# IMX_Power_Regulation.net
KiCad netlist of a schematic drawn in Altium Designer
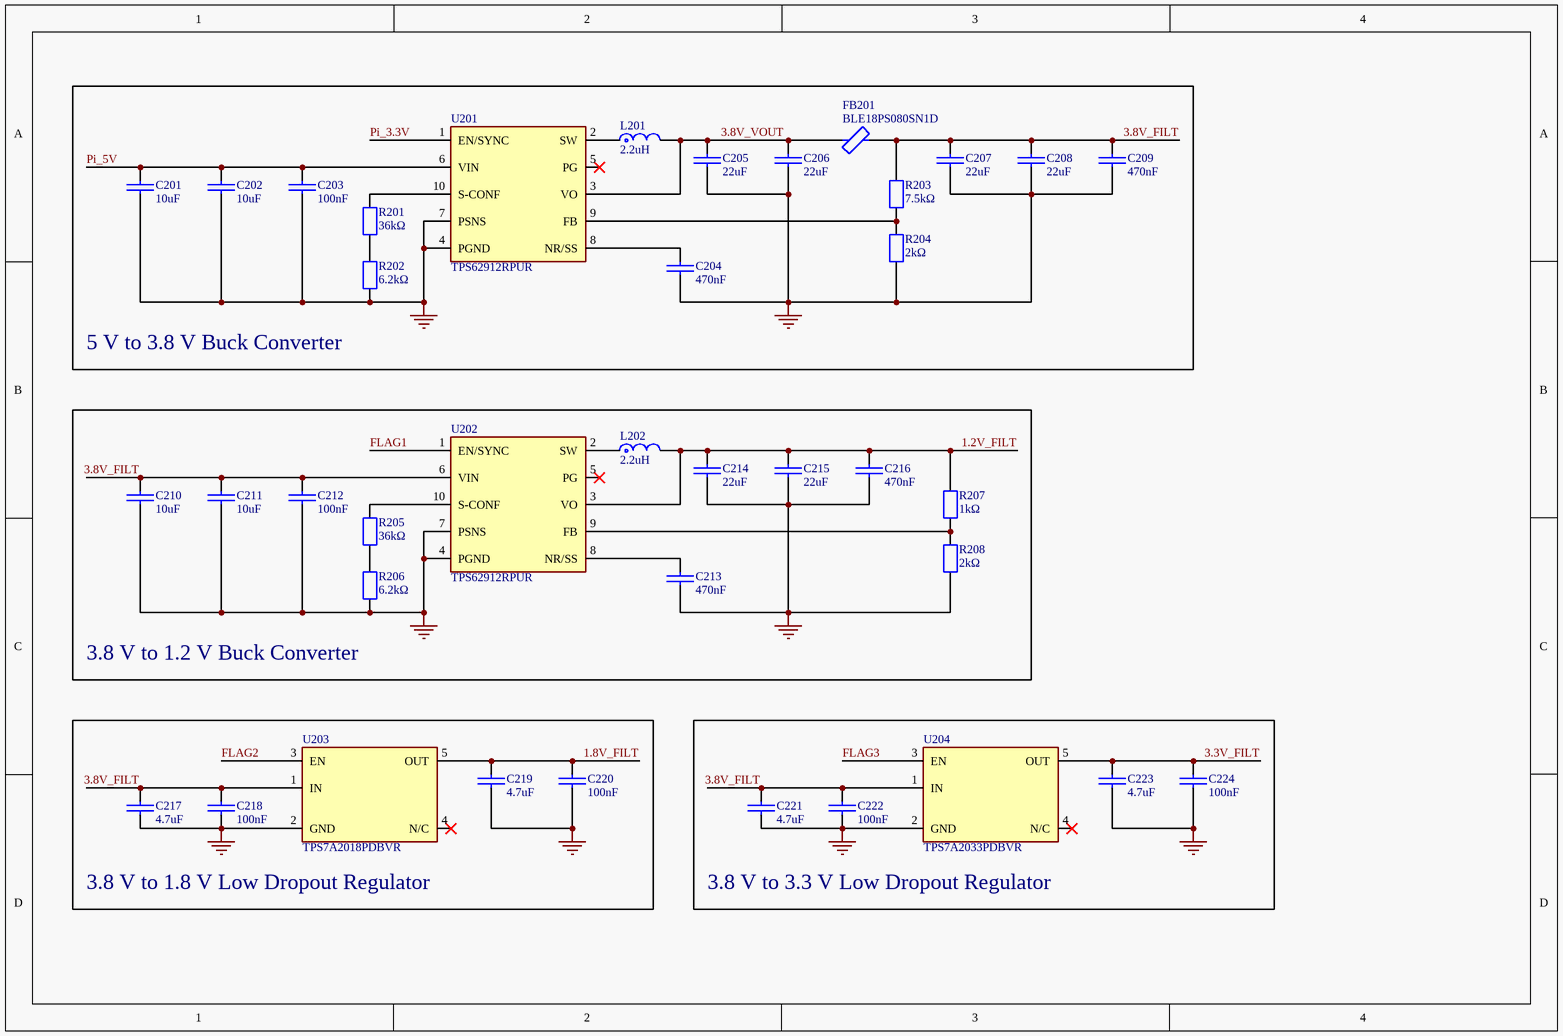
[diagram p0: IMX_Power Regulation.SchDoc]

(export (version "E")
  (design (tool "Eeschema 10.0.6"))
  (components
    (comp (ref "C201")
      (value "10uF")
      (footprint "Capacitor, 0603")
      (description "Ceramic Capacitor, 10V, 10% +/- Tol, X7R, 10uF, SMD, 0603, #GRM188Z71A106KA73D, JLC#C2959727")
      (libsource (lib "Component Library") (part "Capacitor, 0603, 10uF"))
    )
    (comp (ref "C202")
      (value "10uF")
      (footprint "Capacitor, 0603")
      (description "Ceramic Capacitor, 10V, 10% +/- Tol, X7R, 10uF, SMD, 0603, #GRM188Z71A106KA73D, JLC#C2959727")
      (libsource (lib "Component Library") (part "Capacitor, 0603, 10uF"))
    )
    (comp (ref "C203")
      (value "100nF")
      (footprint "Capacitor, 0402")
      (description "Ceramic Capacitor, 16V, 10% +/- Tol, X7R, 0.1uF, SMD, 0402, #CL05B104KO5NNNC, JLC#C1525")
      (libsource (lib "Component Library") (part "Capacitor, 0402, 100nF"))
    )
    (comp (ref "C204")
      (value "470nF")
      (footprint "Capacitor, 0402")
      (libsource (lib "Component Library") (part "Capacitor, 0402, 470nF"))
    )
    (comp (ref "C205")
      (value "22uF")
      (footprint "Capacitor, 0805")
      (libsource (lib "Component Library") (part "Capacitor, 0805, 22uF, X5R"))
    )
    (comp (ref "C206")
      (value "22uF")
      (footprint "Capacitor, 0805")
      (libsource (lib "Component Library") (part "Capacitor, 0805, 22uF, X5R"))
    )
    (comp (ref "C207")
      (value "22uF")
      (footprint "Capacitor, 0805")
      (libsource (lib "Component Library") (part "Capacitor, 0805, 22uF, X5R"))
    )
    (comp (ref "C208")
      (value "22uF")
      (footprint "Capacitor, 0805")
      (libsource (lib "Component Library") (part "Capacitor, 0805, 22uF, X5R"))
    )
    (comp (ref "C209")
      (value "470nF")
      (footprint "Capacitor, 0402")
      (libsource (lib "Component Library") (part "Capacitor, 0402, 470nF"))
    )
    (comp (ref "C210")
      (value "10uF")
      (footprint "Capacitor, 0603")
      (description "Ceramic Capacitor, 10V, 10% +/- Tol, X7R, 10uF, SMD, 0603, #GRM188Z71A106KA73D, JLC#C2959727")
      (libsource (lib "Component Library") (part "Capacitor, 0603, 10uF"))
    )
    (comp (ref "C211")
      (value "10uF")
      (footprint "Capacitor, 0603")
      (description "Ceramic Capacitor, 10V, 10% +/- Tol, X7R, 10uF, SMD, 0603, #GRM188Z71A106KA73D, JLC#C2959727")
      (libsource (lib "Component Library") (part "Capacitor, 0603, 10uF"))
    )
    (comp (ref "C212")
      (value "100nF")
      (footprint "Capacitor, 0402")
      (description "Ceramic Capacitor, 16V, 10% +/- Tol, X7R, 0.1uF, SMD, 0402, #CL05B104KO5NNNC, JLC#C1525")
      (libsource (lib "Component Library") (part "Capacitor, 0402, 100nF"))
    )
    (comp (ref "C213")
      (value "470nF")
      (footprint "Capacitor, 0402")
      (libsource (lib "Component Library") (part "Capacitor, 0402, 470nF"))
    )
    (comp (ref "C214")
      (value "22uF")
      (footprint "Capacitor, 0805")
      (libsource (lib "Component Library") (part "Capacitor, 0805, 22uF, X5R"))
    )
    (comp (ref "C215")
      (value "22uF")
      (footprint "Capacitor, 0805")
      (libsource (lib "Component Library") (part "Capacitor, 0805, 22uF, X5R"))
    )
    (comp (ref "C216")
      (value "470nF")
      (footprint "Capacitor, 0402")
      (libsource (lib "Component Library") (part "Capacitor, 0402, 470nF"))
    )
    (comp (ref "C217")
      (value "4.7uF")
      (footprint "Capacitor, 0603")
      (description "Ceramic Capacitor, 10V, 10% +/- Tol, X7R, 4.7uF, SMD, 0603, #GRM188Z71A475KE15D, JLC#C913474")
      (libsource (lib "Component Library") (part "Capacitor, 0603, 4.7uF"))
    )
    (comp (ref "C218")
      (value "100nF")
      (footprint "Capacitor, 0402")
      (description "Ceramic Capacitor, 16V, 10% +/- Tol, X7R, 0.1uF, SMD, 0402, #CL05B104KO5NNNC, JLC#C1525")
      (libsource (lib "Component Library") (part "Capacitor, 0402, 100nF"))
    )
    (comp (ref "C219")
      (value "4.7uF")
      (footprint "Capacitor, 0603")
      (description "Ceramic Capacitor, 10V, 10% +/- Tol, X7R, 4.7uF, SMD, 0603, #GRM188Z71A475KE15D, JLC#C913474")
      (libsource (lib "Component Library") (part "Capacitor, 0603, 4.7uF"))
    )
    (comp (ref "C220")
      (value "100nF")
      (footprint "Capacitor, 0402")
      (description "Ceramic Capacitor, 16V, 10% +/- Tol, X7R, 0.1uF, SMD, 0402, #CL05B104KO5NNNC, JLC#C1525")
      (libsource (lib "Component Library") (part "Capacitor, 0402, 100nF"))
    )
    (comp (ref "C221")
      (value "4.7uF")
      (footprint "Capacitor, 0603")
      (description "Ceramic Capacitor, 10V, 10% +/- Tol, X7R, 4.7uF, SMD, 0603, #GRM188Z71A475KE15D, JLC#C913474")
      (libsource (lib "Component Library") (part "Capacitor, 0603, 4.7uF"))
    )
    (comp (ref "C222")
      (value "100nF")
      (footprint "Capacitor, 0402")
      (description "Ceramic Capacitor, 16V, 10% +/- Tol, X7R, 0.1uF, SMD, 0402, #CL05B104KO5NNNC, JLC#C1525")
      (libsource (lib "Component Library") (part "Capacitor, 0402, 100nF"))
    )
    (comp (ref "C223")
      (value "4.7uF")
      (footprint "Capacitor, 0603")
      (description "Ceramic Capacitor, 10V, 10% +/- Tol, X7R, 4.7uF, SMD, 0603, #GRM188Z71A475KE15D, JLC#C913474")
      (libsource (lib "Component Library") (part "Capacitor, 0603, 4.7uF"))
    )
    (comp (ref "C224")
      (value "100nF")
      (footprint "Capacitor, 0402")
      (description "Ceramic Capacitor, 16V, 10% +/- Tol, X7R, 0.1uF, SMD, 0402, #CL05B104KO5NNNC, JLC#C1525")
      (libsource (lib "Component Library") (part "Capacitor, 0402, 100nF"))
    )
    (comp (ref "FB201")
      (value "BLE18PS080SN1D")
      (footprint "Ferrite Bead, 0603")
      (description "4mΩ 8.5Ω@100MHz 0603 Ferrite Beads ROHS, #BLE18PS080SN1D, JLC#C3764407")
      (libsource (lib "Component Library") (part "Ferrite Bead, 0603, 4mΩ 8.5Ω@100MHz"))
    )
    (comp (ref "L201")
      (value "2.2uH")
      (footprint "Inductor, 1616")
      (description "2.2uH ±20% 7A 1616 Power Inductors ROHS, #XGL4030-222MEC, JLC#C6616463")
      (fields (field (name "TOLERANCE") "20%"))
      (libsource (lib "Component Library") (part "Inductor, 1616, 2.2uH"))
    )
    (comp (ref "L202")
      (value "2.2uH")
      (footprint "Inductor, 1616")
      (description "2.2uH ±20% 7A 1616 Power Inductors ROHS, #XGL4030-222MEC, JLC#C6616463")
      (fields (field (name "TOLERANCE") "20%"))
      (libsource (lib "Component Library") (part "Inductor, 1616, 2.2uH"))
    )
    (comp (ref "R201")
      (value "36kΩ")
      (footprint "Resistor, 0603, Yageo")
      (libsource (lib "Component Library") (part "Resistor, 0603, 36kΩ"))
    )
    (comp (ref "R202")
      (value "6.2kΩ")
      (footprint "Resistor, 0603, Yageo")
      (libsource (lib "Component Library") (part "Resistor, 0603, 6.2kΩ"))
    )
    (comp (ref "R203")
      (value "7.5kΩ")
      (footprint "Resistor, 0603, Yageo")
      (libsource (lib "Component Library") (part "Resistor, 0603, 7.5kΩ"))
    )
    (comp (ref "R204")
      (value "2kΩ")
      (footprint "Resistor, 0603, Yageo")
      (libsource (lib "Component Library") (part "Resistor, 0603, 2kΩ"))
    )
    (comp (ref "R205")
      (value "36kΩ")
      (footprint "Resistor, 0603, Yageo")
      (libsource (lib "Component Library") (part "Resistor, 0603, 36kΩ"))
    )
    (comp (ref "R206")
      (value "6.2kΩ")
      (footprint "Resistor, 0603, Yageo")
      (libsource (lib "Component Library") (part "Resistor, 0603, 6.2kΩ"))
    )
    (comp (ref "R207")
      (value "1kΩ")
      (footprint "Resistor, 0603, Yageo")
      (libsource (lib "Component Library") (part "Resistor, 0603, 1kΩ"))
    )
    (comp (ref "R208")
      (value "2kΩ")
      (footprint "Resistor, 0603, Yageo")
      (libsource (lib "Component Library") (part "Resistor, 0603, 2kΩ"))
    )
    (comp (ref "U201")
      (value "TPS62912RPUR")
      (footprint "Buck Converter, TPS62912RPUR")
      (description "Step-down type Adjustable 2A 800mV~5.5V 3V~17V VQFN-10-HR(2x2) DC-DC Converters ROHS, JLC#C3198056")
      (fields (field (name "MOUSER PART NUMBER") "595-TPS62912RPUR"))
      (libsource (lib "Component Library") (part "Buck Converter, TPS62912RPUR"))
    )
    (comp (ref "U202")
      (value "TPS62912RPUR")
      (footprint "Buck Converter, TPS62912RPUR")
      (description "Step-down type Adjustable 2A 800mV~5.5V 3V~17V VQFN-10-HR(2x2) DC-DC Converters ROHS, JLC#C3198056")
      (fields (field (name "MOUSER PART NUMBER") "595-TPS62912RPUR"))
      (libsource (lib "Component Library") (part "Buck Converter, TPS62912RPUR"))
    )
    (comp (ref "U203")
      (value "TPS7A2018PDBVR")
      (footprint "TPS7A20 - SOT-23-5L")
      (libsource (lib "Component Library") (part "TPS7A2018PDBVR, 1.8V"))
    )
    (comp (ref "U204")
      (value "TPS7A2033PDBVR")
      (footprint "TPS7A20 - SOT-23-5L")
      (libsource (lib "Component Library") (part "TPS7A2018PDBVR, 3.3V"))
    )
  )
  (nets
    (net (code "1") (name "/1.2V_FILT") (class "Default")
      (node (ref "C214") (pin "1") (pinfunction "1_1") (pintype "passive"))
      (node (ref "C215") (pin "1") (pinfunction "1_1") (pintype "passive"))
      (node (ref "C216") (pin "1") (pinfunction "1_1") (pintype "passive"))
      (node (ref "L202") (pin "2") (pinfunction "2_2") (pintype "passive"))
      (node (ref "R207") (pin "2") (pintype "passive"))
      (node (ref "U202") (pin "3") (pinfunction "VO_3") (pintype "passive"))
    )
    (net (code "2") (name "/1.8V_FILT") (class "Default")
      (node (ref "C219") (pin "1") (pinfunction "1_1") (pintype "passive"))
      (node (ref "C220") (pin "1") (pinfunction "1_1") (pintype "passive"))
      (node (ref "U203") (pin "5") (pinfunction "OUT_5") (pintype "passive"))
    )
    (net (code "3") (name "/3.3V_FILT") (class "Default")
      (node (ref "C223") (pin "1") (pinfunction "1_1") (pintype "passive"))
      (node (ref "C224") (pin "1") (pinfunction "1_1") (pintype "passive"))
      (node (ref "U204") (pin "5") (pinfunction "OUT_5") (pintype "passive"))
    )
    (net (code "4") (name "/3.8V_FILT") (class "Default")
      (node (ref "C207") (pin "1") (pinfunction "1_1") (pintype "passive"))
      (node (ref "C208") (pin "1") (pinfunction "1_1") (pintype "passive"))
      (node (ref "C209") (pin "1") (pinfunction "1_1") (pintype "passive"))
      (node (ref "C210") (pin "1") (pinfunction "1_1") (pintype "passive"))
      (node (ref "C211") (pin "1") (pinfunction "1_1") (pintype "passive"))
      (node (ref "C212") (pin "1") (pinfunction "1_1") (pintype "passive"))
      (node (ref "C217") (pin "1") (pinfunction "1_1") (pintype "passive"))
      (node (ref "C218") (pin "1") (pinfunction "1_1") (pintype "passive"))
      (node (ref "C221") (pin "1") (pinfunction "1_1") (pintype "passive"))
      (node (ref "C222") (pin "1") (pinfunction "1_1") (pintype "passive"))
      (node (ref "FB201") (pin "2") (pinfunction "2_2") (pintype "passive"))
      (node (ref "R203") (pin "2") (pintype "passive"))
      (node (ref "U202") (pin "6") (pinfunction "VIN_6") (pintype "passive"))
      (node (ref "U203") (pin "1") (pinfunction "IN_1") (pintype "passive"))
      (node (ref "U204") (pin "1") (pinfunction "IN_1") (pintype "passive"))
    )
    (net (code "5") (name "/3.8V_VOUT") (class "Default")
      (node (ref "C205") (pin "1") (pinfunction "1_1") (pintype "passive"))
      (node (ref "C206") (pin "1") (pinfunction "1_1") (pintype "passive"))
      (node (ref "FB201") (pin "1") (pinfunction "1_1") (pintype "passive"))
      (node (ref "L201") (pin "2") (pinfunction "2_2") (pintype "passive"))
      (node (ref "U201") (pin "3") (pinfunction "VO_3") (pintype "passive"))
    )
    (net (code "6") (name "/FLAG1") (class "Default")
      (node (ref "U202") (pin "1") (pinfunction "EN/SYNC_1") (pintype "passive"))
    )
    (net (code "7") (name "/FLAG2") (class "Default")
      (node (ref "U203") (pin "3") (pinfunction "EN_3") (pintype "passive"))
    )
    (net (code "8") (name "/FLAG3") (class "Default")
      (node (ref "U204") (pin "3") (pinfunction "EN_3") (pintype "passive"))
    )
    (net (code "9") (name "/Pi_3.3V") (class "Default")
      (node (ref "U201") (pin "1") (pinfunction "EN/SYNC_1") (pintype "passive"))
    )
    (net (code "10") (name "/Pi_5V") (class "Default")
      (node (ref "C201") (pin "1") (pinfunction "1_1") (pintype "passive"))
      (node (ref "C202") (pin "1") (pinfunction "1_1") (pintype "passive"))
      (node (ref "C203") (pin "1") (pinfunction "1_1") (pintype "passive"))
      (node (ref "U201") (pin "6") (pinfunction "VIN_6") (pintype "passive"))
    )
    (net (code "11") (name "GND") (class "Default")
      (node (ref "C201") (pin "2") (pinfunction "2_2") (pintype "passive"))
      (node (ref "C202") (pin "2") (pinfunction "2_2") (pintype "passive"))
      (node (ref "C203") (pin "2") (pinfunction "2_2") (pintype "passive"))
      (node (ref "C204") (pin "2") (pinfunction "2_2") (pintype "passive"))
      (node (ref "C205") (pin "2") (pinfunction "2_2") (pintype "passive"))
      (node (ref "C206") (pin "2") (pinfunction "2_2") (pintype "passive"))
      (node (ref "C207") (pin "2") (pinfunction "2_2") (pintype "passive"))
      (node (ref "C208") (pin "2") (pinfunction "2_2") (pintype "passive"))
      (node (ref "C209") (pin "2") (pinfunction "2_2") (pintype "passive"))
      (node (ref "C210") (pin "2") (pinfunction "2_2") (pintype "passive"))
      (node (ref "C211") (pin "2") (pinfunction "2_2") (pintype "passive"))
      (node (ref "C212") (pin "2") (pinfunction "2_2") (pintype "passive"))
      (node (ref "C213") (pin "2") (pinfunction "2_2") (pintype "passive"))
      (node (ref "C214") (pin "2") (pinfunction "2_2") (pintype "passive"))
      (node (ref "C215") (pin "2") (pinfunction "2_2") (pintype "passive"))
      (node (ref "C216") (pin "2") (pinfunction "2_2") (pintype "passive"))
      (node (ref "C217") (pin "2") (pinfunction "2_2") (pintype "passive"))
      (node (ref "C218") (pin "2") (pinfunction "2_2") (pintype "passive"))
      (node (ref "C219") (pin "2") (pinfunction "2_2") (pintype "passive"))
      (node (ref "C220") (pin "2") (pinfunction "2_2") (pintype "passive"))
      (node (ref "C221") (pin "2") (pinfunction "2_2") (pintype "passive"))
      (node (ref "C222") (pin "2") (pinfunction "2_2") (pintype "passive"))
      (node (ref "C223") (pin "2") (pinfunction "2_2") (pintype "passive"))
      (node (ref "C224") (pin "2") (pinfunction "2_2") (pintype "passive"))
      (node (ref "R202") (pin "1") (pintype "passive"))
      (node (ref "R204") (pin "1") (pintype "passive"))
      (node (ref "R206") (pin "1") (pintype "passive"))
      (node (ref "R208") (pin "1") (pintype "passive"))
      (node (ref "U201") (pin "4") (pinfunction "PGND_4") (pintype "passive"))
      (node (ref "U201") (pin "7") (pinfunction "PSNS_7") (pintype "passive"))
      (node (ref "U202") (pin "4") (pinfunction "PGND_4") (pintype "passive"))
      (node (ref "U202") (pin "7") (pinfunction "PSNS_7") (pintype "passive"))
      (node (ref "U203") (pin "2") (pinfunction "GND_2") (pintype "passive"))
      (node (ref "U204") (pin "2") (pinfunction "GND_2") (pintype "passive"))
    )
    (net (code "12") (name "Net-(R201-Pad1)") (class "Default")
      (node (ref "R201") (pin "1") (pintype "passive"))
      (node (ref "R202") (pin "2") (pintype "passive"))
    )
    (net (code "13") (name "Net-(R205-Pad1)") (class "Default")
      (node (ref "R205") (pin "1") (pintype "passive"))
      (node (ref "R206") (pin "2") (pintype "passive"))
    )
    (net (code "14") (name "Net-(U201-FB)") (class "Default")
      (node (ref "R203") (pin "1") (pintype "passive"))
      (node (ref "R204") (pin "2") (pintype "passive"))
      (node (ref "U201") (pin "9") (pinfunction "FB_9") (pintype "passive"))
    )
    (net (code "15") (name "Net-(U201-NR{slash}SS)") (class "Default")
      (node (ref "C204") (pin "1") (pinfunction "1_1") (pintype "passive"))
      (node (ref "U201") (pin "8") (pinfunction "NR/SS_8") (pintype "passive"))
    )
    (net (code "16") (name "Net-(U201-S-CONF)") (class "Default")
      (node (ref "R201") (pin "2") (pintype "passive"))
      (node (ref "U201") (pin "10") (pinfunction "S-CONF_10") (pintype "passive"))
    )
    (net (code "17") (name "Net-(U201-SW)") (class "Default")
      (node (ref "L201") (pin "1") (pinfunction "1_1") (pintype "passive"))
      (node (ref "U201") (pin "2") (pinfunction "SW_2") (pintype "passive"))
    )
    (net (code "18") (name "Net-(U202-FB)") (class "Default")
      (node (ref "R207") (pin "1") (pintype "passive"))
      (node (ref "R208") (pin "2") (pintype "passive"))
      (node (ref "U202") (pin "9") (pinfunction "FB_9") (pintype "passive"))
    )
    (net (code "19") (name "Net-(U202-NR{slash}SS)") (class "Default")
      (node (ref "C213") (pin "1") (pinfunction "1_1") (pintype "passive"))
      (node (ref "U202") (pin "8") (pinfunction "NR/SS_8") (pintype "passive"))
    )
    (net (code "20") (name "Net-(U202-S-CONF)") (class "Default")
      (node (ref "R205") (pin "2") (pintype "passive"))
      (node (ref "U202") (pin "10") (pinfunction "S-CONF_10") (pintype "passive"))
    )
    (net (code "21") (name "Net-(U202-SW)") (class "Default")
      (node (ref "L202") (pin "1") (pinfunction "1_1") (pintype "passive"))
      (node (ref "U202") (pin "2") (pinfunction "SW_2") (pintype "passive"))
    )
    (net (code "22") (name "unconnected-(U201-PG-Pad5)") (class "Default")
      (node (ref "U201") (pin "5") (pinfunction "PG_5") (pintype "passive+no_connect"))
    )
    (net (code "23") (name "unconnected-(U202-PG-Pad5)") (class "Default")
      (node (ref "U202") (pin "5") (pinfunction "PG_5") (pintype "passive+no_connect"))
    )
    (net (code "24") (name "unconnected-(U203-N{slash}C-Pad4)") (class "Default")
      (node (ref "U203") (pin "4") (pinfunction "N/C_4") (pintype "passive+no_connect"))
    )
    (net (code "25") (name "unconnected-(U204-N{slash}C-Pad4)") (class "Default")
      (node (ref "U204") (pin "4") (pinfunction "N/C_4") (pintype "passive+no_connect"))
    )
  )
)
